# Spectrum_v03_g.net
KiCad netlist of a schematic drawn in EAGLE
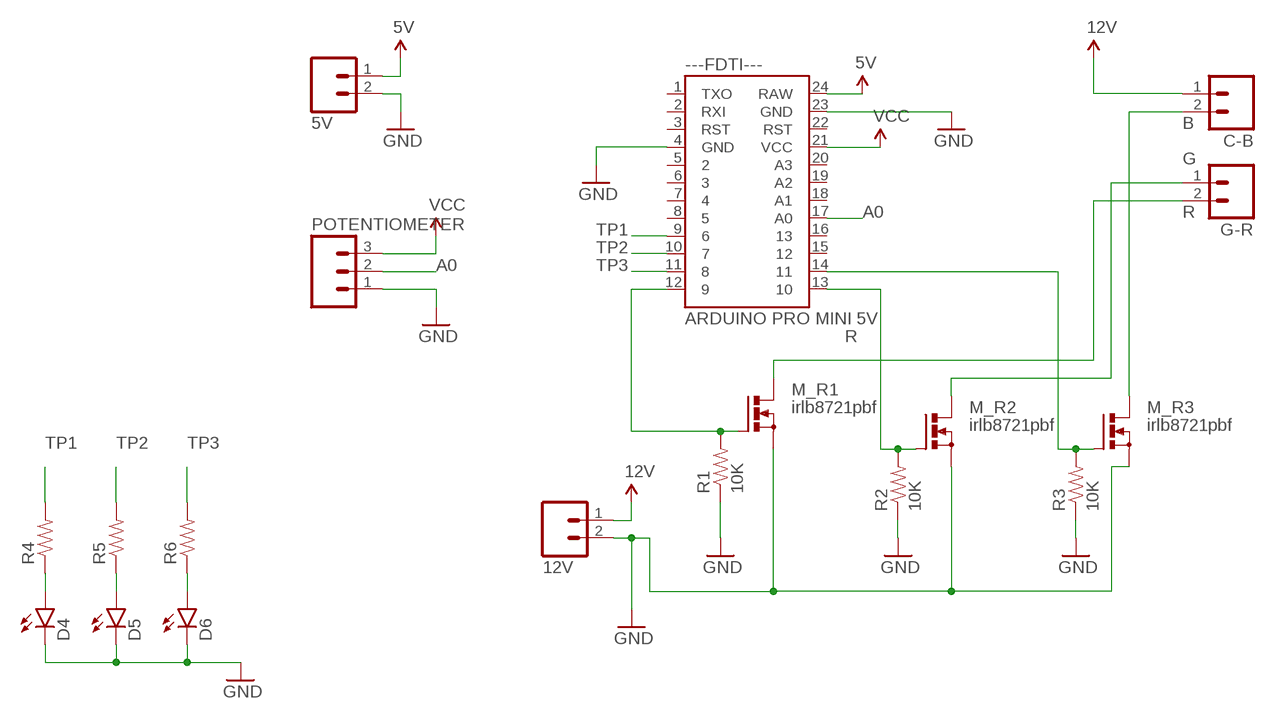
[diagram p0: schematic, sheet 1]

(export (version "E")
  (design (tool "Eeschema 10.0.6"))
  (components
    (comp (ref "---FDTI---")
      (value "ARDUINO PRO MINI 5V")
      (footprint "eagle-import:ARDUINO_MINI")
      (libsource (lib "eagle-import") (part "ARDUINO_MINI"))
    )
    (comp (ref "5V")
      (value "M025MM")
      (footprint "eagle-import:SCREWTERMINAL-5MM-2")
      (libsource (lib "eagle-import") (part "M025MM"))
    )
    (comp (ref "12V")
      (value "M025MM")
      (footprint "eagle-import:SCREWTERMINAL-5MM-2")
      (libsource (lib "eagle-import") (part "M025MM"))
    )
    (comp (ref "C-B")
      (value "M025MM")
      (footprint "eagle-import:SCREWTERMINAL-5MM-2")
      (libsource (lib "eagle-import") (part "M025MM"))
    )
    (comp (ref "D4")
      (value "LED3MM")
      (footprint "eagle-import:LED3MM")
      (libsource (lib "eagle-import") (part "LED3MM"))
    )
    (comp (ref "D5")
      (value "LED3MM")
      (footprint "eagle-import:LED3MM")
      (libsource (lib "eagle-import") (part "LED3MM"))
    )
    (comp (ref "D6")
      (value "LED3MM")
      (footprint "eagle-import:LED3MM")
      (libsource (lib "eagle-import") (part "LED3MM"))
    )
    (comp (ref "G-R")
      (value "M025MM")
      (footprint "eagle-import:SCREWTERMINAL-5MM-2")
      (libsource (lib "eagle-import") (part "M025MM"))
    )
    (comp (ref "M_R1")
      (value "irlb8721pbf")
      (footprint "eagle-import:TO220BV")
      (libsource (lib "eagle-import") (part "PMOSFET_NTO220BV"))
    )
    (comp (ref "M_R2")
      (value "irlb8721pbf")
      (footprint "eagle-import:TO220BV")
      (libsource (lib "eagle-import") (part "PMOSFET_NTO220BV"))
    )
    (comp (ref "M_R3")
      (value "irlb8721pbf")
      (footprint "eagle-import:TO220BV")
      (libsource (lib "eagle-import") (part "PMOSFET_NTO220BV"))
    )
    (comp (ref "POTENTIOMETER")
      (value "M03-SCREW-5MM")
      (footprint "eagle-import:SCREWTERMINAL-5MM-3")
      (libsource (lib "eagle-import") (part "M03-SCREW-5MM"))
    )
    (comp (ref "R1")
      (value "10K")
      (footprint "eagle-import:AXIAL-0.4")
      (libsource (lib "eagle-import") (part "RESISTORPTH-1/4W"))
    )
    (comp (ref "R2")
      (value "10K")
      (footprint "eagle-import:AXIAL-0.4")
      (libsource (lib "eagle-import") (part "RESISTORPTH-1/4W"))
    )
    (comp (ref "R3")
      (value "10K")
      (footprint "eagle-import:AXIAL-0.4")
      (libsource (lib "eagle-import") (part "RESISTORPTH-1/4W"))
    )
    (comp (ref "R4")
      (value "RESISTOREZ")
      (footprint "eagle-import:AXIAL-0.3EZ")
      (libsource (lib "eagle-import") (part "SparkFun-Resistors_RESISTOREZ"))
    )
    (comp (ref "R5")
      (value "RESISTOREZ")
      (footprint "eagle-import:AXIAL-0.3EZ")
      (libsource (lib "eagle-import") (part "SparkFun-Resistors_RESISTOREZ"))
    )
    (comp (ref "R6")
      (value "RESISTOREZ")
      (footprint "eagle-import:AXIAL-0.3EZ")
      (libsource (lib "eagle-import") (part "SparkFun-Resistors_RESISTOREZ"))
    )
  )
  (nets
    (net (code "1") (name "/A0") (class "Default")
      (node (ref "---FDTI---") (pin "17") (pinfunction "A0_17") (pintype "bidirectional"))
      (node (ref "POTENTIOMETER") (pin "2") (pinfunction "2_2") (pintype "passive"))
    )
    (net (code "2") (name "/B") (class "Default")
      (node (ref "C-B") (pin "2") (pinfunction "2_2") (pintype "passive"))
      (node (ref "M_R3") (pin "D") (pinfunction "D_D") (pintype "passive"))
    )
    (net (code "3") (name "/G") (class "Default")
      (node (ref "G-R") (pin "1") (pinfunction "1_1") (pintype "passive"))
      (node (ref "M_R2") (pin "D") (pinfunction "D_D") (pintype "passive"))
    )
    (net (code "4") (name "/R") (class "Default")
      (node (ref "G-R") (pin "2") (pinfunction "2_2") (pintype "passive"))
      (node (ref "M_R1") (pin "D") (pinfunction "D_D") (pintype "passive"))
    )
    (net (code "5") (name "/TP1") (class "Default")
      (node (ref "---FDTI---") (pin "9") (pinfunction "6_9") (pintype "bidirectional"))
      (node (ref "R4") (pin "P$2") (pinfunction "2_P$2") (pintype "passive"))
    )
    (net (code "6") (name "/TP2") (class "Default")
      (node (ref "---FDTI---") (pin "10") (pinfunction "7_10") (pintype "bidirectional"))
      (node (ref "R5") (pin "P$2") (pinfunction "2_P$2") (pintype "passive"))
    )
    (net (code "7") (name "/TP3") (class "Default")
      (node (ref "---FDTI---") (pin "11") (pinfunction "8_11") (pintype "bidirectional"))
      (node (ref "R6") (pin "P$2") (pinfunction "2_P$2") (pintype "passive"))
    )
    (net (code "8") (name "5V") (class "Default")
      (node (ref "---FDTI---") (pin "24") (pinfunction "RAW_24") (pintype "bidirectional"))
      (node (ref "5V") (pin "1") (pinfunction "1_1") (pintype "passive"))
    )
    (net (code "9") (name "12V") (class "Default")
      (node (ref "12V") (pin "1") (pinfunction "1_1") (pintype "passive"))
      (node (ref "C-B") (pin "1") (pinfunction "1_1") (pintype "passive"))
    )
    (net (code "10") (name "GND") (class "Default")
      (node (ref "---FDTI---") (pin "23") (pinfunction "GND_23") (pintype "bidirectional"))
      (node (ref "---FDTI---") (pin "4") (pinfunction "GND_4") (pintype "bidirectional"))
      (node (ref "12V") (pin "2") (pinfunction "2_2") (pintype "passive"))
      (node (ref "5V") (pin "2") (pinfunction "2_2") (pintype "passive"))
      (node (ref "D4") (pin "K") (pinfunction "C_K") (pintype "passive"))
      (node (ref "D5") (pin "K") (pinfunction "C_K") (pintype "passive"))
      (node (ref "D6") (pin "K") (pinfunction "C_K") (pintype "passive"))
      (node (ref "M_R1") (pin "S") (pinfunction "S_S") (pintype "passive"))
      (node (ref "M_R2") (pin "S") (pinfunction "S_S") (pintype "passive"))
      (node (ref "M_R3") (pin "S") (pinfunction "S_S") (pintype "passive"))
      (node (ref "POTENTIOMETER") (pin "1") (pinfunction "1_1") (pintype "passive"))
      (node (ref "R1") (pin "P$1") (pinfunction "1_P$1") (pintype "passive"))
      (node (ref "R2") (pin "P$1") (pinfunction "1_P$1") (pintype "passive"))
      (node (ref "R3") (pin "P$1") (pinfunction "1_P$1") (pintype "passive"))
    )
    (net (code "11") (name "Net-(---FDTI----9)") (class "Default")
      (node (ref "---FDTI---") (pin "12") (pinfunction "9_12") (pintype "bidirectional"))
      (node (ref "M_R1") (pin "G") (pinfunction "G_G") (pintype "passive"))
      (node (ref "R1") (pin "P$2") (pinfunction "2_P$2") (pintype "passive"))
    )
    (net (code "12") (name "Net-(---FDTI----10)") (class "Default")
      (node (ref "---FDTI---") (pin "13") (pinfunction "10_13") (pintype "bidirectional"))
      (node (ref "M_R2") (pin "G") (pinfunction "G_G") (pintype "passive"))
      (node (ref "R2") (pin "P$2") (pinfunction "2_P$2") (pintype "passive"))
    )
    (net (code "13") (name "Net-(---FDTI----11)") (class "Default")
      (node (ref "---FDTI---") (pin "14") (pinfunction "11_14") (pintype "bidirectional"))
      (node (ref "M_R3") (pin "G") (pinfunction "G_G") (pintype "passive"))
      (node (ref "R3") (pin "P$2") (pinfunction "2_P$2") (pintype "passive"))
    )
    (net (code "14") (name "Net-(R4-1)") (class "Default")
      (node (ref "D4") (pin "A") (pinfunction "A_A") (pintype "passive"))
      (node (ref "R4") (pin "P$1") (pinfunction "1_P$1") (pintype "passive"))
    )
    (net (code "15") (name "Net-(R5-1)") (class "Default")
      (node (ref "D5") (pin "A") (pinfunction "A_A") (pintype "passive"))
      (node (ref "R5") (pin "P$1") (pinfunction "1_P$1") (pintype "passive"))
    )
    (net (code "16") (name "Net-(R6-1)") (class "Default")
      (node (ref "D6") (pin "A") (pinfunction "A_A") (pintype "passive"))
      (node (ref "R6") (pin "P$1") (pinfunction "1_P$1") (pintype "passive"))
    )
    (net (code "17") (name "VCC") (class "Default")
      (node (ref "---FDTI---") (pin "21") (pinfunction "VCC_21") (pintype "bidirectional"))
      (node (ref "POTENTIOMETER") (pin "3") (pinfunction "3_3") (pintype "passive"))
    )
    (net (code "18") (name "unconnected-(---FDTI----2-Pad5)") (class "Default")
      (node (ref "---FDTI---") (pin "5") (pinfunction "2_5") (pintype "bidirectional"))
    )
    (net (code "19") (name "unconnected-(---FDTI----3-Pad6)") (class "Default")
      (node (ref "---FDTI---") (pin "6") (pinfunction "3_6") (pintype "bidirectional"))
    )
    (net (code "20") (name "unconnected-(---FDTI----4-Pad7)") (class "Default")
      (node (ref "---FDTI---") (pin "7") (pinfunction "4_7") (pintype "bidirectional"))
    )
    (net (code "21") (name "unconnected-(---FDTI----5-Pad8)") (class "Default")
      (node (ref "---FDTI---") (pin "8") (pinfunction "5_8") (pintype "bidirectional"))
    )
    (net (code "22") (name "unconnected-(---FDTI----12-Pad15)") (class "Default")
      (node (ref "---FDTI---") (pin "15") (pinfunction "12_15") (pintype "bidirectional"))
    )
    (net (code "23") (name "unconnected-(---FDTI----13-Pad16)") (class "Default")
      (node (ref "---FDTI---") (pin "16") (pinfunction "13_16") (pintype "bidirectional"))
    )
    (net (code "24") (name "unconnected-(---FDTI----A1-Pad18)") (class "Default")
      (node (ref "---FDTI---") (pin "18") (pinfunction "A1_18") (pintype "bidirectional"))
    )
    (net (code "25") (name "unconnected-(---FDTI----A2-Pad19)") (class "Default")
      (node (ref "---FDTI---") (pin "19") (pinfunction "A2_19") (pintype "bidirectional"))
    )
    (net (code "26") (name "unconnected-(---FDTI----A3-Pad20)") (class "Default")
      (node (ref "---FDTI---") (pin "20") (pinfunction "A3_20") (pintype "bidirectional"))
    )
    (net (code "27") (name "unconnected-(---FDTI----RST-Pad3)") (class "Default")
      (node (ref "---FDTI---") (pin "3") (pinfunction "RST_3") (pintype "bidirectional"))
    )
    (net (code "28") (name "unconnected-(---FDTI----RST-Pad22)") (class "Default")
      (node (ref "---FDTI---") (pin "22") (pinfunction "RST_22") (pintype "bidirectional"))
    )
    (net (code "29") (name "unconnected-(---FDTI----RXI-Pad2)") (class "Default")
      (node (ref "---FDTI---") (pin "2") (pinfunction "RXI_2") (pintype "bidirectional"))
    )
    (net (code "30") (name "unconnected-(---FDTI----TXO-Pad1)") (class "Default")
      (node (ref "---FDTI---") (pin "1") (pinfunction "TXO_1") (pintype "bidirectional"))
    )
  )
)
